# AstroEQ_SMD_V4_8.net
KiCad netlist of a schematic drawn in EAGLE
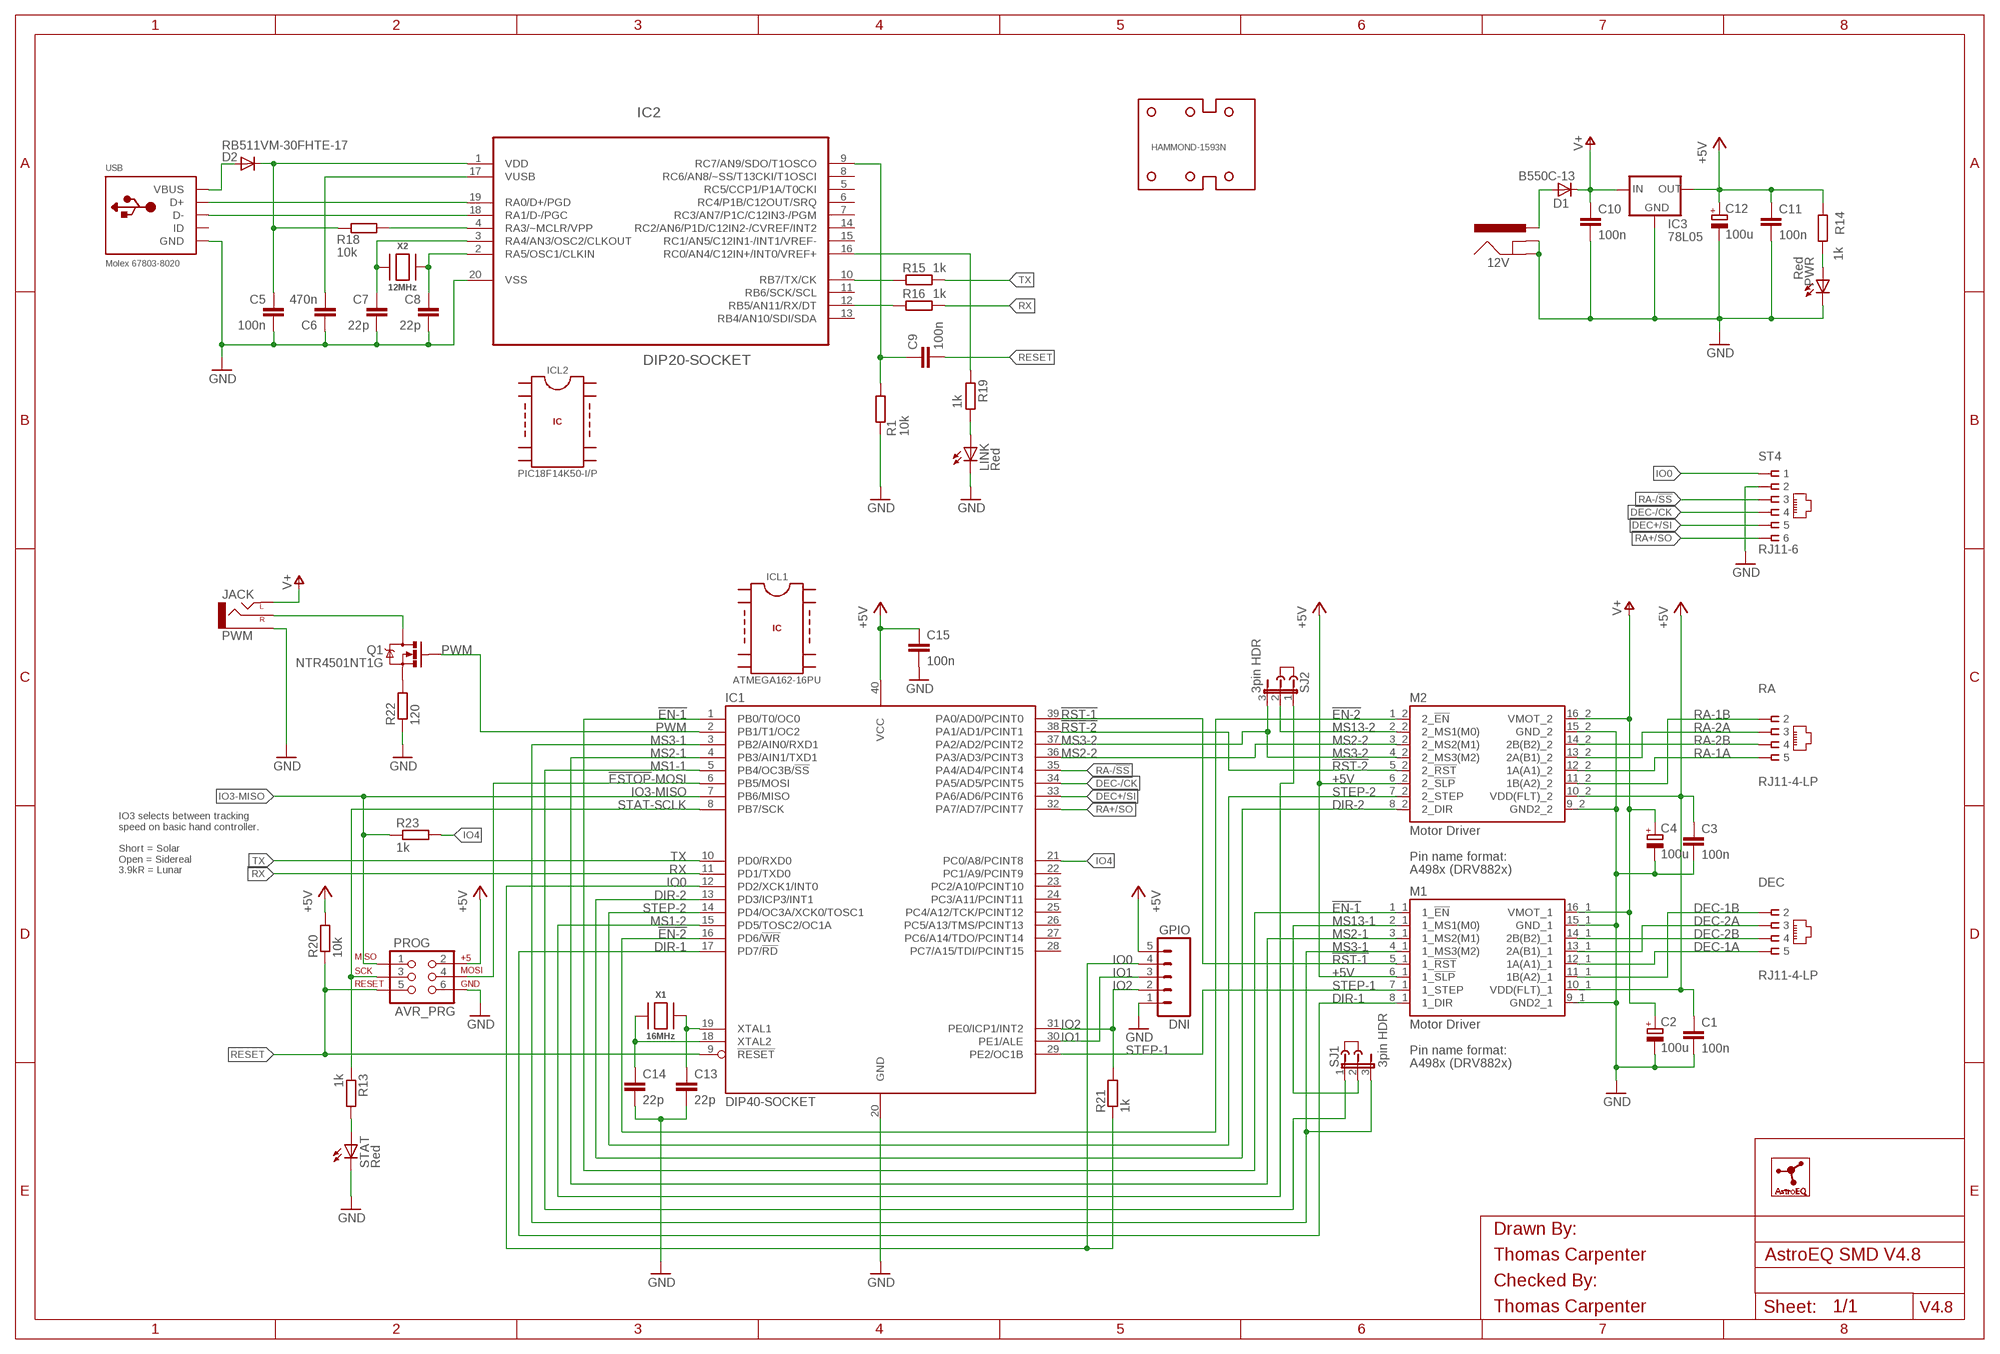
[diagram p0: schematic, sheet 1]

(export (version "E")
  (design (tool "Eeschema 10.0.6"))
  (components
    (comp (ref "12V")
      (value "POWER_JACKPTH")
      (footprint "eagle-import:POWER_JACK_PTH")
      (fields (field (name "MF") "MULTICOMP") (field (name "MPN") "MJ-179PH"))
      (libsource (lib "eagle-import") (part "POWER_JACKPTH"))
    )
    (comp (ref "C1")
      (value "100n")
      (footprint "eagle-import:C0603")
      (fields (field (name "MF") "MULTICOMP") (field (name "MPN") "MC0603F104Z250CT"))
      (libsource (lib "eagle-import") (part "C-EUC0603"))
    )
    (comp (ref "C2")
      (value "100u")
      (footprint "eagle-import:PANASONIC_D")
      (fields (field (name "MF") "WURTH ELEKTRONIK") (field (name "MPN") "865080545012"))
      (libsource (lib "eagle-import") (part "CPOL-EUD"))
    )
    (comp (ref "C3")
      (value "100n")
      (footprint "eagle-import:C0603")
      (fields (field (name "MF") "MULTICOMP") (field (name "MPN") "MC0603F104Z250CT"))
      (libsource (lib "eagle-import") (part "C-EUC0603"))
    )
    (comp (ref "C4")
      (value "100u")
      (footprint "eagle-import:PANASONIC_D")
      (fields (field (name "MF") "WURTH ELEKTRONIK") (field (name "MPN") "865080545012"))
      (libsource (lib "eagle-import") (part "CPOL-EUD"))
    )
    (comp (ref "C5")
      (value "100n")
      (footprint "eagle-import:C0603")
      (fields (field (name "MF") "MULTICOMP") (field (name "MPN") "MC0603F104Z250CT"))
      (libsource (lib "eagle-import") (part "C-EUC0603"))
    )
    (comp (ref "C6")
      (value "470n")
      (footprint "eagle-import:C0603")
      (fields (field (name "MF") "MULTICOMP") (field (name "MPN") "MC0603F474Z160CT"))
      (libsource (lib "eagle-import") (part "C-EUC0603"))
    )
    (comp (ref "C7")
      (value "22p")
      (footprint "eagle-import:C0603")
      (fields (field (name "MF") "MULTICOMP") (field (name "MPN") "MC0603N220J500CT"))
      (libsource (lib "eagle-import") (part "C-EUC0603"))
    )
    (comp (ref "C8")
      (value "22p")
      (footprint "eagle-import:C0603")
      (fields (field (name "MF") "MULTICOMP") (field (name "MPN") "MC0603N220J500CT"))
      (libsource (lib "eagle-import") (part "C-EUC0603"))
    )
    (comp (ref "C9")
      (value "100n")
      (footprint "eagle-import:C0603")
      (fields (field (name "MF") "MULTICOMP") (field (name "MPN") "MC0603F104Z250CT"))
      (libsource (lib "eagle-import") (part "C-EUC0603"))
    )
    (comp (ref "C10")
      (value "100n")
      (footprint "eagle-import:C0603")
      (fields (field (name "MF") "MULTICOMP") (field (name "MPN") "MC0603F104Z250CT"))
      (libsource (lib "eagle-import") (part "C-EUC0603"))
    )
    (comp (ref "C11")
      (value "100n")
      (footprint "eagle-import:C0603")
      (fields (field (name "MF") "MULTICOMP") (field (name "MPN") "MC0603F104Z250CT"))
      (libsource (lib "eagle-import") (part "C-EUC0603"))
    )
    (comp (ref "C12")
      (value "100u")
      (footprint "eagle-import:PANASONIC_D")
      (fields (field (name "MF") "WURTH ELEKTRONIK") (field (name "MPN") "865080545012"))
      (libsource (lib "eagle-import") (part "CPOL-EUD"))
    )
    (comp (ref "C13")
      (value "22p")
      (footprint "eagle-import:C0603")
      (fields (field (name "MF") "MULTICOMP") (field (name "MPN") "MC0603N220J500CT"))
      (libsource (lib "eagle-import") (part "C-EUC0603"))
    )
    (comp (ref "C14")
      (value "22p")
      (footprint "eagle-import:C0603")
      (fields (field (name "MF") "MULTICOMP") (field (name "MPN") "MC0603N220J500CT"))
      (libsource (lib "eagle-import") (part "C-EUC0603"))
    )
    (comp (ref "C15")
      (value "100n")
      (footprint "eagle-import:C0603")
      (fields (field (name "MF") "MULTICOMP") (field (name "MPN") "MC0603F104Z250CT"))
      (libsource (lib "eagle-import") (part "C-EUC0603"))
    )
    (comp (ref "D1")
      (value "B550C-13")
      (footprint "eagle-import:SMC")
      (fields (field (name "MF") "DIODES INC.") (field (name "MPN") "B550C-13-F"))
      (libsource (lib "eagle-import") (part "DIODE-SMC"))
    )
    (comp (ref "D2")
      (value "RB511VM-30FHTE-17")
      (footprint "eagle-import:SOD-323")
      (fields (field (name "MF") "ROHM"))
      (libsource (lib "eagle-import") (part "DIODESOD"))
    )
    (comp (ref "DEC")
      (value "RJ11-4-LP")
      (footprint "eagle-import:RJ11-NO_SHIELD-4-LP")
      (fields (field (name "MF") "MOLEX") (field (name "MPN") "95501-2641"))
      (libsource (lib "eagle-import") (part "RJ11-4-LP"))
    )
    (comp (ref "GPIO")
      (value "DNI")
      (footprint "eagle-import:1X05")
      (libsource (lib "eagle-import") (part "M05PTH"))
    )
    (comp (ref "HAMMOND-1593N")
      (value "HAMMOND-1593N-4HOLE")
      (footprint "eagle-import:HAMMOND-1593N4HOLES")
      (fields (field (name "MF") "HAMMOND") (field (name "MPN") "1593NBK"))
      (libsource (lib "eagle-import") (part "HAMMOND-1593N-4HOLE"))
    )
    (comp (ref "IC1")
      (value "DIP40-SOCKET")
      (footprint "eagle-import:DIL40")
      (fields (field (name "MF") "MULTICOMP") (field (name "MPN") "2227MC-40-06-05-F1"))
      (libsource (lib "eagle-import") (part "ATMEGA162-16PU"))
    )
    (comp (ref "IC2")
      (value "DIP20-SOCKET")
      (footprint "eagle-import:DIL20-SKT")
      (fields (field (name "MF") "MULTICOMP"))
      (libsource (lib "eagle-import") (part "PIC18F14K50/P-SKT-I"))
    )
    (comp (ref "IC3")
      (value "78L05")
      (footprint "eagle-import:SOT89")
      (fields (field (name "MF") "STMICROELECTRONICS") (field (name "MPN") "L78L05ACUTR"))
      (libsource (lib "eagle-import") (part "V_REG_78XX-SOT89"))
    )
    (comp (ref "ICL1")
      (value "ATMEGA162-16PU")
      (footprint "eagle-import:IC")
      (fields (field (name "MF") "ATMEL"))
      (libsource (lib "eagle-import") (part "IC"))
    )
    (comp (ref "ICL2")
      (value "PIC18F14K50-I/P")
      (footprint "eagle-import:IC")
      (fields (field (name "MF") "MICROCHIP"))
      (libsource (lib "eagle-import") (part "IC"))
    )
    (comp (ref "J2")
      (value "DNI")
      (footprint "eagle-import:JUMP")
      (fields (field (name "MF") "3M") (field (name "MPN") "969102-0000-DA"))
      (libsource (lib "eagle-import") (part "JUMPER"))
    )
    (comp (ref "J3")
      (value "DNI")
      (footprint "eagle-import:JUMP")
      (fields (field (name "MF") "3M") (field (name "MPN") "969102-0000-DA"))
      (libsource (lib "eagle-import") (part "JUMPER"))
    )
    (comp (ref "LINK")
      (value "Red")
      (footprint "eagle-import:SML1206-SIDE")
      (fields (field (name "MF") "WURTH ELEKTRONIK") (field (name "MPN") "155124RS73200"))
      (libsource (lib "eagle-import") (part "LED-1206-SIDE"))
    )
    (comp (ref "LOGO1")
      (value "DNI")
      (footprint "eagle-import:ASTROEQ-SMALL")
      (libsource (lib "eagle-import") (part "ASTROEQ5MM"))
    )
    (comp (ref "M1")
      (value "Motor Driver")
      (footprint "eagle-import:CARRIER-HV-DUAL")
      (fields (field (name "MF") "SAMTEC") (field (name "MPN") "CES-116-01-T-S"))
      (libsource (lib "eagle-import") (part "A4983-DUAL-HV"))
    )
    (comp (ref "M2")
      (value "Motor Driver")
      (footprint "eagle-import:CARRIER-LV-DUAL")
      (fields (field (name "MF") "SAMTEC") (field (name "MPN") "CES-116-01-T-S"))
      (libsource (lib "eagle-import") (part "A4983-DUAL-LV"))
    )
    (comp (ref "PROG")
      (value "AVR_PRG")
      (footprint "eagle-import:2X3")
      (fields (field (name "MF") "HARWIN") (field (name "MPN") "M20-9980346"))
      (libsource (lib "eagle-import") (part "AVR_SPI_PRG_6PTH"))
    )
    (comp (ref "PWM")
      (value "JACK")
      (footprint "eagle-import:AUDIO-JACK")
      (fields (field (name "MF") "CLIFF ELECTRONIC COMPONENTS") (field (name "MPN") "FC68131"))
      (libsource (lib "eagle-import") (part "AUDIO-JACKPTH"))
    )
    (comp (ref "PWR")
      (value "Red")
      (footprint "eagle-import:SML1206-SIDE")
      (fields (field (name "MF") "WURTH ELEKTRONIK") (field (name "MPN") "155124RS73200"))
      (libsource (lib "eagle-import") (part "LED-1206-SIDE"))
    )
    (comp (ref "Q1")
      (value "NTR4501NT1G")
      (footprint "eagle-import:SOT23-3")
      (fields (field (name "MF") "ON SEMICONDUCTOR"))
      (libsource (lib "eagle-import") (part "MOSFET-NCHANNELSMD"))
    )
    (comp (ref "R1")
      (value "10k")
      (footprint "eagle-import:R0603")
      (fields (field (name "MF") "MULTICOMP") (field (name "MPN") "MCWR06X1002FTL"))
      (libsource (lib "eagle-import") (part "R-EU_R0603"))
    )
    (comp (ref "R13")
      (value "1k")
      (footprint "eagle-import:R0603")
      (fields (field (name "MF") "MULTICOMP") (field (name "MPN") "MCWR06X1001FTL"))
      (libsource (lib "eagle-import") (part "R-EU_R0603"))
    )
    (comp (ref "R14")
      (value "1k")
      (footprint "eagle-import:R0603")
      (fields (field (name "MF") "MULTICOMP") (field (name "MPN") "MCWR06X1001FTL"))
      (libsource (lib "eagle-import") (part "R-EU_R0603"))
    )
    (comp (ref "R15")
      (value "1k")
      (footprint "eagle-import:R0603")
      (fields (field (name "MF") "MULTICOMP") (field (name "MPN") "MCWR06X1001FTL"))
      (libsource (lib "eagle-import") (part "R-EU_R0603"))
    )
    (comp (ref "R16")
      (value "1k")
      (footprint "eagle-import:R0603")
      (fields (field (name "MF") "MULTICOMP") (field (name "MPN") "MCWR06X1001FTL"))
      (libsource (lib "eagle-import") (part "R-EU_R0603"))
    )
    (comp (ref "R18")
      (value "10k")
      (footprint "eagle-import:R0603")
      (fields (field (name "MF") "MULTICOMP") (field (name "MPN") "MCWR06X1002FTL"))
      (libsource (lib "eagle-import") (part "R-EU_R0603"))
    )
    (comp (ref "R19")
      (value "1k")
      (footprint "eagle-import:R0603")
      (fields (field (name "MF") "MULTICOMP") (field (name "MPN") "MCWR06X1001FTL"))
      (libsource (lib "eagle-import") (part "R-EU_R0603"))
    )
    (comp (ref "R20")
      (value "10k")
      (footprint "eagle-import:R0603")
      (fields (field (name "MF") "MULTICOMP") (field (name "MPN") "MCWR06X1002FTL"))
      (libsource (lib "eagle-import") (part "R-EU_R0603"))
    )
    (comp (ref "R21")
      (value "1k")
      (footprint "eagle-import:R0603")
      (fields (field (name "MF") "MULTICOMP") (field (name "MPN") "MCWR06X1001FTL"))
      (libsource (lib "eagle-import") (part "R-EU_R0603"))
    )
    (comp (ref "R22")
      (value "120")
      (footprint "eagle-import:R0805")
      (fields (field (name "MF") "MULTICOMP") (field (name "MPN") "MCWR08X1200FTL"))
      (libsource (lib "eagle-import") (part "R-EU_R0805"))
    )
    (comp (ref "R23")
      (value "1k")
      (footprint "eagle-import:R0603")
      (fields (field (name "MF") "MULTICOMP") (field (name "MPN") "MCWR06X1001FTL"))
      (libsource (lib "eagle-import") (part "R-EU_R0603"))
    )
    (comp (ref "RA")
      (value "RJ11-4-LP")
      (footprint "eagle-import:RJ11-NO_SHIELD-4-LP")
      (fields (field (name "MF") "MOLEX") (field (name "MPN") "95501-2641"))
      (libsource (lib "eagle-import") (part "RJ11-4-LP"))
    )
    (comp (ref "SJ1")
      (value "3pin HDR")
      (footprint "eagle-import:JP2")
      (fields (field (name "MF") "HARWIN") (field (name "MPN") "M20-9990345."))
      (libsource (lib "eagle-import") (part "JP2E"))
    )
    (comp (ref "SJ2")
      (value "3pin HDR")
      (footprint "eagle-import:JP2")
      (fields (field (name "MF") "HARWIN") (field (name "MPN") "M20-9990345."))
      (libsource (lib "eagle-import") (part "JP2E"))
    )
    (comp (ref "ST4")
      (value "RJ11-6")
      (footprint "eagle-import:RJ11-NO_SHIELD-LP")
      (fields (field (name "MF") "MOLEX") (field (name "MPN") "95501-2661"))
      (libsource (lib "eagle-import") (part "RJ11-LP"))
    )
    (comp (ref "STAT")
      (value "Red")
      (footprint "eagle-import:SML1206-SIDE")
      (fields (field (name "MF") "WURTH ELEKTRONIK") (field (name "MPN") "155124RS73200"))
      (libsource (lib "eagle-import") (part "LED-1206-SIDE"))
    )
    (comp (ref "USB")
      (value "Molex 67803-8020")
      (footprint "eagle-import:USB-MINIAB")
      (fields (field (name "MF") "MOLEX") (field (name "MPN") "67803-8020"))
      (libsource (lib "eagle-import") (part "USBMINIAB"))
    )
    (comp (ref "X1")
      (value "16MHz")
      (footprint "eagle-import:NX5032")
      (fields (field (name "MF") "TXC") (field (name "MPN") "7A-16.000MAAJ-T"))
      (libsource (lib "eagle-import") (part "XTALNX5032"))
    )
    (comp (ref "X2")
      (value "12MHz")
      (footprint "eagle-import:NX5032")
      (fields (field (name "MF") "TXC") (field (name "MPN") "7A-12.000MAAJ-T"))
      (libsource (lib "eagle-import") (part "XTALNX5032"))
    )
  )
  (nets
    (net (code "1") (name "+5V") (class "Default")
      (node (ref "C1") (pin "1") (pinfunction "1_1") (pintype "passive"))
      (node (ref "C11") (pin "1") (pinfunction "1_1") (pintype "passive"))
      (node (ref "C12") (pin "+") (pinfunction "+_+") (pintype "passive"))
      (node (ref "C15") (pin "1") (pinfunction "1_1") (pintype "passive"))
      (node (ref "C3") (pin "1") (pinfunction "1_1") (pintype "passive"))
      (node (ref "GPIO") (pin "5") (pinfunction "5_5") (pintype "passive"))
      (node (ref "IC1") (pin "40") (pinfunction "VCC_40") (pintype "power_in"))
      (node (ref "IC3") (pin "1") (pinfunction "OUT_1") (pintype "power_in"))
      (node (ref "M1") (pin "10_1") (pinfunction "VDD(FLT)_1_10_1") (pintype "power_in"))
      (node (ref "M1") (pin "10_2") (pinfunction "VDD(FLT)_2_10_2") (pintype "power_in"))
      (node (ref "M2") (pin "6_1") (pinfunction "1_~{SLP}_6_1") (pintype "input"))
      (node (ref "M2") (pin "6_2") (pinfunction "2_~{SLP}_6_2") (pintype "input"))
      (node (ref "PROG") (pin "2") (pinfunction "2_2") (pintype "passive"))
      (node (ref "R14") (pin "1") (pinfunction "1_1") (pintype "passive"))
      (node (ref "R20") (pin "2") (pinfunction "2_2") (pintype "passive"))
    )
    (net (code "2") (name "/DEC-1A") (class "Default")
      (node (ref "DEC") (pin "5") (pinfunction "5_5") (pintype "passive"))
      (node (ref "M1") (pin "12_1") (pinfunction "1A(A1)_1_12_1") (pintype "output"))
    )
    (net (code "3") (name "/DEC-1B") (class "Default")
      (node (ref "DEC") (pin "2") (pinfunction "2_2") (pintype "passive"))
      (node (ref "M1") (pin "11_1") (pinfunction "1B(A2)_1_11_1") (pintype "output"))
    )
    (net (code "4") (name "/DEC-2A") (class "Default")
      (node (ref "DEC") (pin "3") (pinfunction "3_3") (pintype "passive"))
      (node (ref "M1") (pin "13_1") (pinfunction "2A(B1)_1_13_1") (pintype "output"))
    )
    (net (code "5") (name "/DEC-2B") (class "Default")
      (node (ref "DEC") (pin "4") (pinfunction "4_4") (pintype "passive"))
      (node (ref "M1") (pin "14_1") (pinfunction "2B(B2)_1_14_1") (pintype "output"))
    )
    (net (code "6") (name "/DIR-1") (class "Default")
      (node (ref "IC1") (pin "17") (pinfunction "PD7/~{RD}_17") (pintype "bidirectional"))
      (node (ref "M2") (pin "8_1") (pinfunction "1_DIR_8_1") (pintype "input"))
    )
    (net (code "7") (name "/DIR-2") (class "Default")
      (node (ref "IC1") (pin "13") (pinfunction "PD3/ICP3/INT1_13") (pintype "bidirectional"))
      (node (ref "M2") (pin "8_2") (pinfunction "2_DIR_8_2") (pintype "input"))
    )
    (net (code "8") (name "/IO1") (class "Default")
      (node (ref "GPIO") (pin "3") (pinfunction "3_3") (pintype "passive"))
      (node (ref "IC1") (pin "30") (pinfunction "PE1/ALE_30") (pintype "bidirectional"))
    )
    (net (code "9") (name "/IO2") (class "Default")
      (node (ref "GPIO") (pin "2") (pinfunction "2_2") (pintype "passive"))
      (node (ref "IC1") (pin "31") (pinfunction "PE0/ICP1/INT2_31") (pintype "bidirectional"))
      (node (ref "R21") (pin "2") (pinfunction "2_2") (pintype "passive"))
    )
    (net (code "10") (name "/MS1-1") (class "Default")
      (node (ref "IC1") (pin "5") (pinfunction "PB4/OC3B/~{SS}_5") (pintype "bidirectional"))
      (node (ref "SJ1") (pin "1") (pinfunction "1_1") (pintype "passive"))
    )
    (net (code "11") (name "/MS1-2") (class "Default")
      (node (ref "IC1") (pin "15") (pinfunction "PD5/TOSC2/OC1A_15") (pintype "bidirectional"))
      (node (ref "SJ2") (pin "1") (pinfunction "1_1") (pintype "passive"))
    )
    (net (code "12") (name "/MS2-1") (class "Default")
      (node (ref "IC1") (pin "4") (pinfunction "PB3/AIN1/TXD1_4") (pintype "bidirectional"))
      (node (ref "M2") (pin "3_1") (pinfunction "1_MS2(M1)_3_1") (pintype "input"))
    )
    (net (code "13") (name "/MS2-2") (class "Default")
      (node (ref "IC1") (pin "36") (pinfunction "PA3/AD3/PCINT3_36") (pintype "bidirectional"))
      (node (ref "M2") (pin "3_2") (pinfunction "2_MS2(M1)_3_2") (pintype "input"))
    )
    (net (code "14") (name "/MS3-1") (class "Default")
      (node (ref "IC1") (pin "3") (pinfunction "PB2/AIN0/RXD1_3") (pintype "bidirectional"))
      (node (ref "M2") (pin "4_1") (pinfunction "1_MS3(M2)_4_1") (pintype "input"))
      (node (ref "SJ1") (pin "3") (pinfunction "3_3") (pintype "passive"))
    )
    (net (code "15") (name "/MS3-2") (class "Default")
      (node (ref "IC1") (pin "37") (pinfunction "PA2/AD2/PCINT2_37") (pintype "bidirectional"))
      (node (ref "M2") (pin "4_2") (pinfunction "2_MS3(M2)_4_2") (pintype "input"))
      (node (ref "SJ2") (pin "3") (pinfunction "3_3") (pintype "passive"))
    )
    (net (code "16") (name "/MS13-1") (class "Default")
      (node (ref "M2") (pin "2_1") (pinfunction "1_MS1(M0)_2_1") (pintype "input"))
      (node (ref "SJ1") (pin "2") (pinfunction "2_2") (pintype "passive"))
    )
    (net (code "17") (name "/MS13-2") (class "Default")
      (node (ref "M2") (pin "2_2") (pinfunction "2_MS1(M0)_2_2") (pintype "input"))
      (node (ref "SJ2") (pin "2") (pinfunction "2_2") (pintype "passive"))
    )
    (net (code "18") (name "/PWM") (class "Default")
      (node (ref "IC1") (pin "2") (pinfunction "PB1/T1/OC2_2") (pintype "bidirectional"))
      (node (ref "Q1") (pin "1") (pinfunction "G_1") (pintype "passive"))
    )
    (net (code "19") (name "/RA-1A") (class "Default")
      (node (ref "M1") (pin "12_2") (pinfunction "1A(A1)_2_12_2") (pintype "output"))
      (node (ref "RA") (pin "5") (pinfunction "5_5") (pintype "passive"))
    )
    (net (code "20") (name "/RA-1B") (class "Default")
      (node (ref "M1") (pin "11_2") (pinfunction "1B(A2)_2_11_2") (pintype "output"))
      (node (ref "RA") (pin "2") (pinfunction "2_2") (pintype "passive"))
    )
    (net (code "21") (name "/RA-2A") (class "Default")
      (node (ref "M1") (pin "13_2") (pinfunction "2A(B1)_2_13_2") (pintype "output"))
      (node (ref "RA") (pin "3") (pinfunction "3_3") (pintype "passive"))
    )
    (net (code "22") (name "/RA-2B") (class "Default")
      (node (ref "M1") (pin "14_2") (pinfunction "2B(B2)_2_14_2") (pintype "output"))
      (node (ref "RA") (pin "4") (pinfunction "4_4") (pintype "passive"))
    )
    (net (code "23") (name "/RA-{slash}~{SS}") (class "Default")
      (node (ref "IC1") (pin "35") (pinfunction "PA4/AD4/PCINT4_35") (pintype "bidirectional"))
      (node (ref "ST4") (pin "3") (pinfunction "3_3") (pintype "passive"))
    )
    (net (code "24") (name "/STAT-SCLK") (class "Default")
      (node (ref "IC1") (pin "8") (pinfunction "PB7/SCK_8") (pintype "bidirectional"))
      (node (ref "PROG") (pin "3") (pinfunction "3_3") (pintype "passive"))
      (node (ref "R13") (pin "1") (pinfunction "1_1") (pintype "passive"))
    )
    (net (code "25") (name "/STEP-1") (class "Default")
      (node (ref "IC1") (pin "29") (pinfunction "PE2/OC1B_29") (pintype "bidirectional"))
      (node (ref "M2") (pin "7_1") (pinfunction "1_STEP_7_1") (pintype "input"))
    )
    (net (code "26") (name "/STEP-2") (class "Default")
      (node (ref "IC1") (pin "14") (pinfunction "PD4/OC3A/XCK0/TOSC1_14") (pintype "bidirectional"))
      (node (ref "M2") (pin "7_2") (pinfunction "2_STEP_7_2") (pintype "input"))
    )
    (net (code "27") (name "/~{EN-1}") (class "Default")
      (node (ref "IC1") (pin "1") (pinfunction "PB0/T0/OC0_1") (pintype "bidirectional"))
      (node (ref "M2") (pin "1_1") (pinfunction "1_~{EN}_1_1") (pintype "input"))
    )
    (net (code "28") (name "/~{EN-2}") (class "Default")
      (node (ref "IC1") (pin "16") (pinfunction "PD6/~{WR}_16") (pintype "bidirectional"))
      (node (ref "M2") (pin "1_2") (pinfunction "2_~{EN}_1_2") (pintype "input"))
    )
    (net (code "29") (name "/~{ESTOP}-MOSI") (class "Default")
      (node (ref "IC1") (pin "6") (pinfunction "PB5/MOSI_6") (pintype "bidirectional"))
      (node (ref "PROG") (pin "4") (pinfunction "4_4") (pintype "passive"))
    )
    (net (code "30") (name "/~{RST-1}") (class "Default")
      (node (ref "IC1") (pin "39") (pinfunction "PA0/AD0/PCINT0_39") (pintype "bidirectional"))
      (node (ref "M2") (pin "5_1") (pinfunction "1_~{RST}_5_1") (pintype "input"))
    )
    (net (code "31") (name "/~{RST-2}") (class "Default")
      (node (ref "IC1") (pin "38") (pinfunction "PA1/AD1/PCINT1_38") (pintype "bidirectional"))
      (node (ref "M2") (pin "5_2") (pinfunction "2_~{RST}_5_2") (pintype "input"))
    )
    (net (code "32") (name "DEC+{slash}SI") (class "Default")
      (node (ref "IC1") (pin "33") (pinfunction "PA6/AD6/PCINT6_33") (pintype "bidirectional"))
      (node (ref "ST4") (pin "5") (pinfunction "5_5") (pintype "passive"))
    )
    (net (code "33") (name "DEC-{slash}CK") (class "Default")
      (node (ref "IC1") (pin "34") (pinfunction "PA5/AD5/PCINT5_34") (pintype "bidirectional"))
      (node (ref "ST4") (pin "4") (pinfunction "4_4") (pintype "passive"))
    )
    (net (code "34") (name "GND") (class "Default")
      (node (ref "12V") (pin "GND") (pinfunction "GND_GND") (pintype "bidirectional"))
      (node (ref "12V") (pin "GNDBREAK") (pinfunction "GNDBREAK_GNDBREAK") (pintype "bidirectional"))
      (node (ref "C1") (pin "2") (pinfunction "2_2") (pintype "passive"))
      (node (ref "C10") (pin "2") (pinfunction "2_2") (pintype "passive"))
      (node (ref "C11") (pin "2") (pinfunction "2_2") (pintype "passive"))
      (node (ref "C12") (pin "-") (pinfunction "-_-") (pintype "passive"))
      (node (ref "C13") (pin "2") (pinfunction "2_2") (pintype "passive"))
      (node (ref "C14") (pin "2") (pinfunction "2_2") (pintype "passive"))
      (node (ref "C15") (pin "2") (pinfunction "2_2") (pintype "passive"))
      (node (ref "C2") (pin "-") (pinfunction "-_-") (pintype "passive"))
      (node (ref "C3") (pin "2") (pinfunction "2_2") (pintype "passive"))
      (node (ref "C4") (pin "-") (pinfunction "-_-") (pintype "passive"))
      (node (ref "C5") (pin "2") (pinfunction "2_2") (pintype "passive"))
      (node (ref "C6") (pin "1") (pinfunction "1_1") (pintype "passive"))
      (node (ref "C7") (pin "2") (pinfunction "2_2") (pintype "passive"))
      (node (ref "C8") (pin "2") (pinfunction "2_2") (pintype "passive"))
      (node (ref "GPIO") (pin "1") (pinfunction "1_1") (pintype "passive"))
      (node (ref "IC1") (pin "20") (pinfunction "GND_20") (pintype "power_in"))
      (node (ref "IC2") (pin "20") (pinfunction "VSS_20") (pintype "power_in"))
      (node (ref "IC3") (pin "2") (pinfunction "GND_2") (pintype "power_in"))
      (node (ref "IC3") (pin "4") (pinfunction "GND_4") (pintype "power_in"))
      (node (ref "LINK") (pin "C") (pinfunction "C_C") (pintype "passive"))
      (node (ref "LINK") (pin "E") (pinfunction "C_E") (pintype "passive"))
      (node (ref "M1") (pin "15_1") (pinfunction "GND_1_15_1") (pintype "power_in"))
      (node (ref "M1") (pin "15_2") (pinfunction "GND_2_15_2") (pintype "power_in"))
      (node (ref "M1") (pin "9_1") (pinfunction "GND2_1_9_1") (pintype "power_in"))
      (node (ref "M1") (pin "9_2") (pinfunction "GND2_2_9_2") (pintype "power_in"))
      (node (ref "PROG") (pin "6") (pinfunction "6_6") (pintype "passive"))
      (node (ref "PWM") (pin "SLEEVE") (pinfunction "SLEEVE_SLEEVE") (pintype "bidirectional"))
      (node (ref "PWR") (pin "C") (pinfunction "C_C") (pintype "passive"))
      (node (ref "PWR") (pin "E") (pinfunction "C_E") (pintype "passive"))
      (node (ref "R1") (pin "2") (pinfunction "2_2") (pintype "passive"))
      (node (ref "R22") (pin "1") (pinfunction "1_1") (pintype "passive"))
      (node (ref "ST4") (pin "2") (pinfunction "2_2") (pintype "passive"))
      (node (ref "STAT") (pin "C") (pinfunction "C_C") (pintype "passive"))
      (node (ref "STAT") (pin "E") (pinfunction "C_E") (pintype "passive"))
      (node (ref "USB") (pin "GND") (pinfunction "GND_GND") (pintype "power_in"))
      (node (ref "USB") (pin "GND1") (pinfunction "GND_GND1") (pintype "power_in"))
      (node (ref "USB") (pin "GND2") (pinfunction "GND_GND2") (pintype "power_in"))
      (node (ref "USB") (pin "GND3") (pinfunction "GND_GND3") (pintype "power_in"))
      (node (ref "USB") (pin "GND4") (pinfunction "GND_GND4") (pintype "power_in"))
    )
    (net (code "35") (name "IO0") (class "Default")
      (node (ref "GPIO") (pin "4") (pinfunction "4_4") (pintype "passive"))
      (node (ref "IC1") (pin "12") (pinfunction "PD2/XCK1/INT0_12") (pintype "bidirectional"))
      (node (ref "R21") (pin "1") (pinfunction "1_1") (pintype "passive"))
      (node (ref "ST4") (pin "1") (pinfunction "1_1") (pintype "passive"))
    )
    (net (code "36") (name "IO3-MISO") (class "Default")
      (node (ref "IC1") (pin "7") (pinfunction "PB6/MISO_7") (pintype "bidirectional"))
      (node (ref "PROG") (pin "1") (pinfunction "1_1") (pintype "passive"))
      (node (ref "R23") (pin "1") (pinfunction "1_1") (pintype "passive"))
    )
    (net (code "37") (name "IO4") (class "Default")
      (node (ref "IC1") (pin "21") (pinfunction "PC0/A8/PCINT8_21") (pintype "bidirectional"))
      (node (ref "R23") (pin "2") (pinfunction "2_2") (pintype "passive"))
    )
    (net (code "38") (name "Net-(12V-PadPWR)") (class "Default")
      (node (ref "12V") (pin "PWR") (pinfunction "PWR_PWR") (pintype "bidirectional"))
      (node (ref "D1") (pin "A") (pinfunction "A_A") (pintype "passive"))
    )
    (net (code "39") (name "Net-(D2-A)") (class "Default")
      (node (ref "D2") (pin "2") (pinfunction "A_2") (pintype "passive"))
      (node (ref "USB") (pin "VBUS") (pinfunction "VBUS_VBUS") (pintype "power_in"))
    )
    (net (code "40") (name "Net-(D2-C)") (class "Default")
      (node (ref "C5") (pin "1") (pinfunction "1_1") (pintype "passive"))
      (node (ref "D2") (pin "1") (pinfunction "C_1") (pintype "passive"))
      (node (ref "IC2") (pin "1") (pinfunction "VDD_1") (pintype "power_in"))
      (node (ref "R18") (pin "2") (pinfunction "2_2") (pintype "passive"))
    )
    (net (code "41") (name "Net-(IC1-XTAL1)") (class "Default")
      (node (ref "C13") (pin "1") (pinfunction "1_1") (pintype "passive"))
      (node (ref "IC1") (pin "19") (pinfunction "XTAL1_19") (pintype "input"))
      (node (ref "X1") (pin "P$2") (pinfunction "P$2_P$2") (pintype "bidirectional"))
    )
    (net (code "42") (name "Net-(IC1-XTAL2)") (class "Default")
      (node (ref "C14") (pin "1") (pinfunction "1_1") (pintype "passive"))
      (node (ref "IC1") (pin "18") (pinfunction "XTAL2_18") (pintype "input"))
      (node (ref "X1") (pin "P$1") (pinfunction "P$1_P$1") (pintype "bidirectional"))
    )
    (net (code "43") (name "Net-(IC2-RA0{slash}D+{slash}PGD)") (class "Default")
      (node (ref "IC2") (pin "19") (pinfunction "RA0/D+/PGD_19") (pintype "bidirectional"))
      (node (ref "USB") (pin "D+") (pinfunction "D+_D+") (pintype "bidirectional"))
    )
    (net (code "44") (name "Net-(IC2-RA1{slash}D-{slash}PGC)") (class "Default")
      (node (ref "IC2") (pin "18") (pinfunction "RA1/D-/PGC_18") (pintype "bidirectional"))
      (node (ref "USB") (pin "D-") (pinfunction "D-_D-") (pintype "bidirectional"))
    )
    (net (code "45") (name "Net-(IC2-RA3{slash}~{MCLR{slash}VPP})") (class "Default")
      (node (ref "IC2") (pin "4") (pinfunction "RA3/~{MCLR/VPP}_4") (pintype "input"))
      (node (ref "R18") (pin "1") (pinfunction "1_1") (pintype "passive"))
    )
    (net (code "46") (name "Net-(IC2-RA4{slash}AN3{slash}OSC2{slash}CLKOUT)") (class "Default")
      (node (ref "C7") (pin "1") (pinfunction "1_1") (pintype "passive"))
      (node (ref "IC2") (pin "3") (pinfunction "RA4/AN3/OSC2/CLKOUT_3") (pintype "bidirectional"))
      (node (ref "X2") (pin "P$1") (pinfunction "P$1_P$1") (pintype "bidirectional"))
    )
    (net (code "47") (name "Net-(IC2-RA5{slash}OSC1{slash}CLKIN)") (class "Default")
      (node (ref "C8") (pin "1") (pinfunction "1_1") (pintype "passive"))
      (node (ref "IC2") (pin "2") (pinfunction "RA5/OSC1/CLKIN_2") (pintype "bidirectional"))
      (node (ref "X2") (pin "P$2") (pinfunction "P$2_P$2") (pintype "bidirectional"))
    )
    (net (code "48") (name "Net-(IC2-RB5{slash}AN11{slash}RX{slash}DT)") (class "Default")
      (node (ref "IC2") (pin "12") (pinfunction "RB5/AN11/RX/DT_12") (pintype "bidirectional"))
      (node (ref "R16") (pin "2") (pinfunction "2_2") (pintype "passive"))
    )
    (net (code "49") (name "Net-(IC2-RB7{slash}TX{slash}CK)") (class "Default")
      (node (ref "IC2") (pin "10") (pinfunction "RB7/TX/CK_10") (pintype "bidirectional"))
      (node (ref "R15") (pin "2") (pinfunction "2_2") (pintype "passive"))
    )
    (net (code "50") (name "Net-(IC2-RC0{slash}AN4{slash}C12IN+{slash}INT0{slash}VREF+)") (class "Default")
      (node (ref "IC2") (pin "16") (pinfunction "RC0/AN4/C12IN+/INT0/VREF+_16") (pintype "bidirectional"))
      (node (ref "R19") (pin "2") (pinfunction "2_2") (pintype "passive"))
    )
    (net (code "51") (name "Net-(IC2-RC7{slash}AN9{slash}SDO{slash}T1OSCO)") (class "Default")
      (node (ref "C9") (pin "1") (pinfunction "1_1") (pintype "passive"))
      (node (ref "IC2") (pin "9") (pinfunction "RC7/AN9/SDO/T1OSCO_9") (pintype "bidirectional"))
      (node (ref "R1") (pin "1") (pinfunction "1_1") (pintype "passive"))
    )
    (net (code "52") (name "Net-(IC2-VUSB)") (class "Default")
      (node (ref "C6") (pin "2") (pinfunction "2_2") (pintype "passive"))
      (node (ref "IC2") (pin "17") (pinfunction "VUSB_17") (pintype "power_in"))
    )
    (net (code "53") (name "Net-(LINK-PadA)") (class "Default")
      (node (ref "LINK") (pin "A") (pinfunction "A_A") (pintype "passive"))
      (node (ref "R19") (pin "1") (pinfunction "1_1") (pintype "passive"))
    )
    (net (code "54") (name "Net-(PWM-RIGHT)") (class "Default")
      (node (ref "PWM") (pin "RING") (pinfunction "RIGHT_RING") (pintype "bidirectional"))
      (node (ref "Q1") (pin "3") (pinfunction "D_3") (pintype "passive"))
    )
    (net (code "55") (name "Net-(PWR-PadA)") (class "Default")
      (node (ref "PWR") (pin "A") (pinfunction "A_A") (pintype "passive"))
      (node (ref "R14") (pin "2") (pinfunction "2_2") (pintype "passive"))
    )
    (net (code "56") (name "Net-(Q1-S)") (class "Default")
      (node (ref "Q1") (pin "2") (pinfunction "S_2") (pintype "passive"))
      (node (ref "R22") (pin "2") (pinfunction "2_2") (pintype "passive"))
    )
    (net (code "57") (name "Net-(R13-Pad2)") (class "Default")
      (node (ref "R13") (pin "2") (pinfunction "2_2") (pintype "passive"))
      (node (ref "STAT") (pin "A") (pinfunction "A_A") (pintype "passive"))
    )
    (net (code "58") (name "RA+{slash}SO") (class "Default")
      (node (ref "IC1") (pin "32") (pinfunction "PA7/AD7/PCINT7_32") (pintype "bidirectional"))
      (node (ref "ST4") (pin "6") (pinfunction "6_6") (pintype "passive"))
    )
    (net (code "59") (name "RESET") (class "Default")
      (node (ref "C9") (pin "2") (pinfunction "2_2") (pintype "passive"))
      (node (ref "IC1") (pin "9") (pinfunction "~{RESET}_9") (pintype "input"))
      (node (ref "PROG") (pin "5") (pinfunction "5_5") (pintype "passive"))
      (node (ref "R20") (pin "1") (pinfunction "1_1") (pintype "passive"))
    )
    (net (code "60") (name "RX") (class "Default")
      (node (ref "IC1") (pin "11") (pinfunction "PD1/TXD0_11") (pintype "bidirectional"))
      (node (ref "R16") (pin "1") (pinfunction "1_1") (pintype "passive"))
    )
    (net (code "61") (name "TX") (class "Default")
      (node (ref "IC1") (pin "10") (pinfunction "PD0/RXD0_10") (pintype "bidirectional"))
      (node (ref "R15") (pin "1") (pinfunction "1_1") (pintype "passive"))
    )
    (net (code "62") (name "V+") (class "Default")
      (node (ref "C10") (pin "1") (pinfunction "1_1") (pintype "passive"))
      (node (ref "C2") (pin "+") (pinfunction "+_+") (pintype "passive"))
      (node (ref "C4") (pin "+") (pinfunction "+_+") (pintype "passive"))
      (node (ref "D1") (pin "C") (pinfunction "C_C") (pintype "passive"))
      (node (ref "IC3") (pin "3") (pinfunction "IN_3") (pintype "power_in"))
      (node (ref "M1") (pin "16_1") (pinfunction "VMOT_1_16_1") (pintype "power_in"))
      (node (ref "M1") (pin "16_2") (pinfunction "VMOT_2_16_2") (pintype "power_in"))
      (node (ref "PWM") (pin "TIP") (pinfunction "LEFT_TIP") (pintype "bidirectional"))
    )
    (net (code "63") (name "unconnected-(IC1-PC1{slash}A9{slash}PCINT9-Pad22)") (class "Default")
      (node (ref "IC1") (pin "22") (pinfunction "PC1/A9/PCINT9_22") (pintype "bidirectional"))
    )
    (net (code "64") (name "unconnected-(IC1-PC2{slash}A10{slash}PCINT10-Pad23)") (class "Default")
      (node (ref "IC1") (pin "23") (pinfunction "PC2/A10/PCINT10_23") (pintype "bidirectional"))
    )
    (net (code "65") (name "unconnected-(IC1-PC3{slash}A11{slash}PCINT11-Pad24)") (class "Default")
      (node (ref "IC1") (pin "24") (pinfunction "PC3/A11/PCINT11_24") (pintype "bidirectional"))
    )
    (net (code "66") (name "unconnected-(IC1-PC4{slash}A12{slash}TCK{slash}PCINT12-Pad25)") (class "Default")
      (node (ref "IC1") (pin "25") (pinfunction "PC4/A12/TCK/PCINT12_25") (pintype "bidirectional"))
    )
    (net (code "67") (name "unconnected-(IC1-PC5{slash}A13{slash}TMS{slash}PCINT13-Pad26)") (class "Default")
      (node (ref "IC1") (pin "26") (pinfunction "PC5/A13/TMS/PCINT13_26") (pintype "bidirectional"))
    )
    (net (code "68") (name "unconnected-(IC1-PC6{slash}A14{slash}TDO{slash}PCINT14-Pad27)") (class "Default")
      (node (ref "IC1") (pin "27") (pinfunction "PC6/A14/TDO/PCINT14_27") (pintype "bidirectional"))
    )
    (net (code "69") (name "unconnected-(IC1-PC7{slash}A15{slash}TDI{slash}PCINT15-Pad28)") (class "Default")
      (node (ref "IC1") (pin "28") (pinfunction "PC7/A15/TDI/PCINT15_28") (pintype "bidirectional"))
    )
    (net (code "70") (name "unconnected-(IC2-RB4{slash}AN10{slash}SDI{slash}SDA-Pad13)") (class "Default")
      (node (ref "IC2") (pin "13") (pinfunction "RB4/AN10/SDI/SDA_13") (pintype "bidirectional"))
    )
    (net (code "71") (name "unconnected-(IC2-RB6{slash}SCK{slash}SCL-Pad11)") (class "Default")
      (node (ref "IC2") (pin "11") (pinfunction "RB6/SCK/SCL_11") (pintype "bidirectional"))
    )
    (net (code "72") (name "unconnected-(IC2-RC1{slash}AN5{slash}C12IN1-{slash}INT1{slash}VREF--Pad15)") (class "Default")
      (node (ref "IC2") (pin "15") (pinfunction "RC1/AN5/C12IN1-/INT1/VREF-_15") (pintype "bidirectional"))
    )
    (net (code "73") (name "unconnected-(IC2-RC2{slash}AN6{slash}P1D{slash}C12IN2-{slash}CVREF{slash}INT2-Pad14)") (class "Default")
      (node (ref "IC2") (pin "14") (pinfunction "RC2/AN6/P1D/C12IN2-/CVREF/INT2_14") (pintype "bidirectional"))
    )
    (net (code "74") (name "unconnected-(IC2-RC3{slash}AN7{slash}P1C{slash}C12IN3-{slash}PGM-Pad7)") (class "Default")
      (node (ref "IC2") (pin "7") (pinfunction "RC3/AN7/P1C/C12IN3-/PGM_7") (pintype "bidirectional"))
    )
    (net (code "75") (name "unconnected-(IC2-RC4{slash}P1B{slash}C12OUT{slash}SRQ-Pad6)") (class "Default")
      (node (ref "IC2") (pin "6") (pinfunction "RC4/P1B/C12OUT/SRQ_6") (pintype "bidirectional"))
    )
    (net (code "76") (name "unconnected-(IC2-RC5{slash}CCP1{slash}P1A{slash}T0CKI-Pad5)") (class "Default")
      (node (ref "IC2") (pin "5") (pinfunction "RC5/CCP1/P1A/T0CKI_5") (pintype "bidirectional"))
    )
    (net (code "77") (name "unconnected-(IC2-RC6{slash}AN8{slash}~{SS{slash}T13CKI{slash}T1OSCI}-Pad8)") (class "Default")
      (node (ref "IC2") (pin "8") (pinfunction "RC6/AN8/~{SS/T13CKI/T1OSCI}_8") (pintype "bidirectional"))
    )
    (net (code "78") (name "unconnected-(USB-PadID)") (class "Default")
      (node (ref "USB") (pin "ID") (pinfunction "ID_ID") (pintype "bidirectional"))
    )
  )
)
